# Sata_Drives.net
KiCad netlist of a schematic drawn in Altium Designer
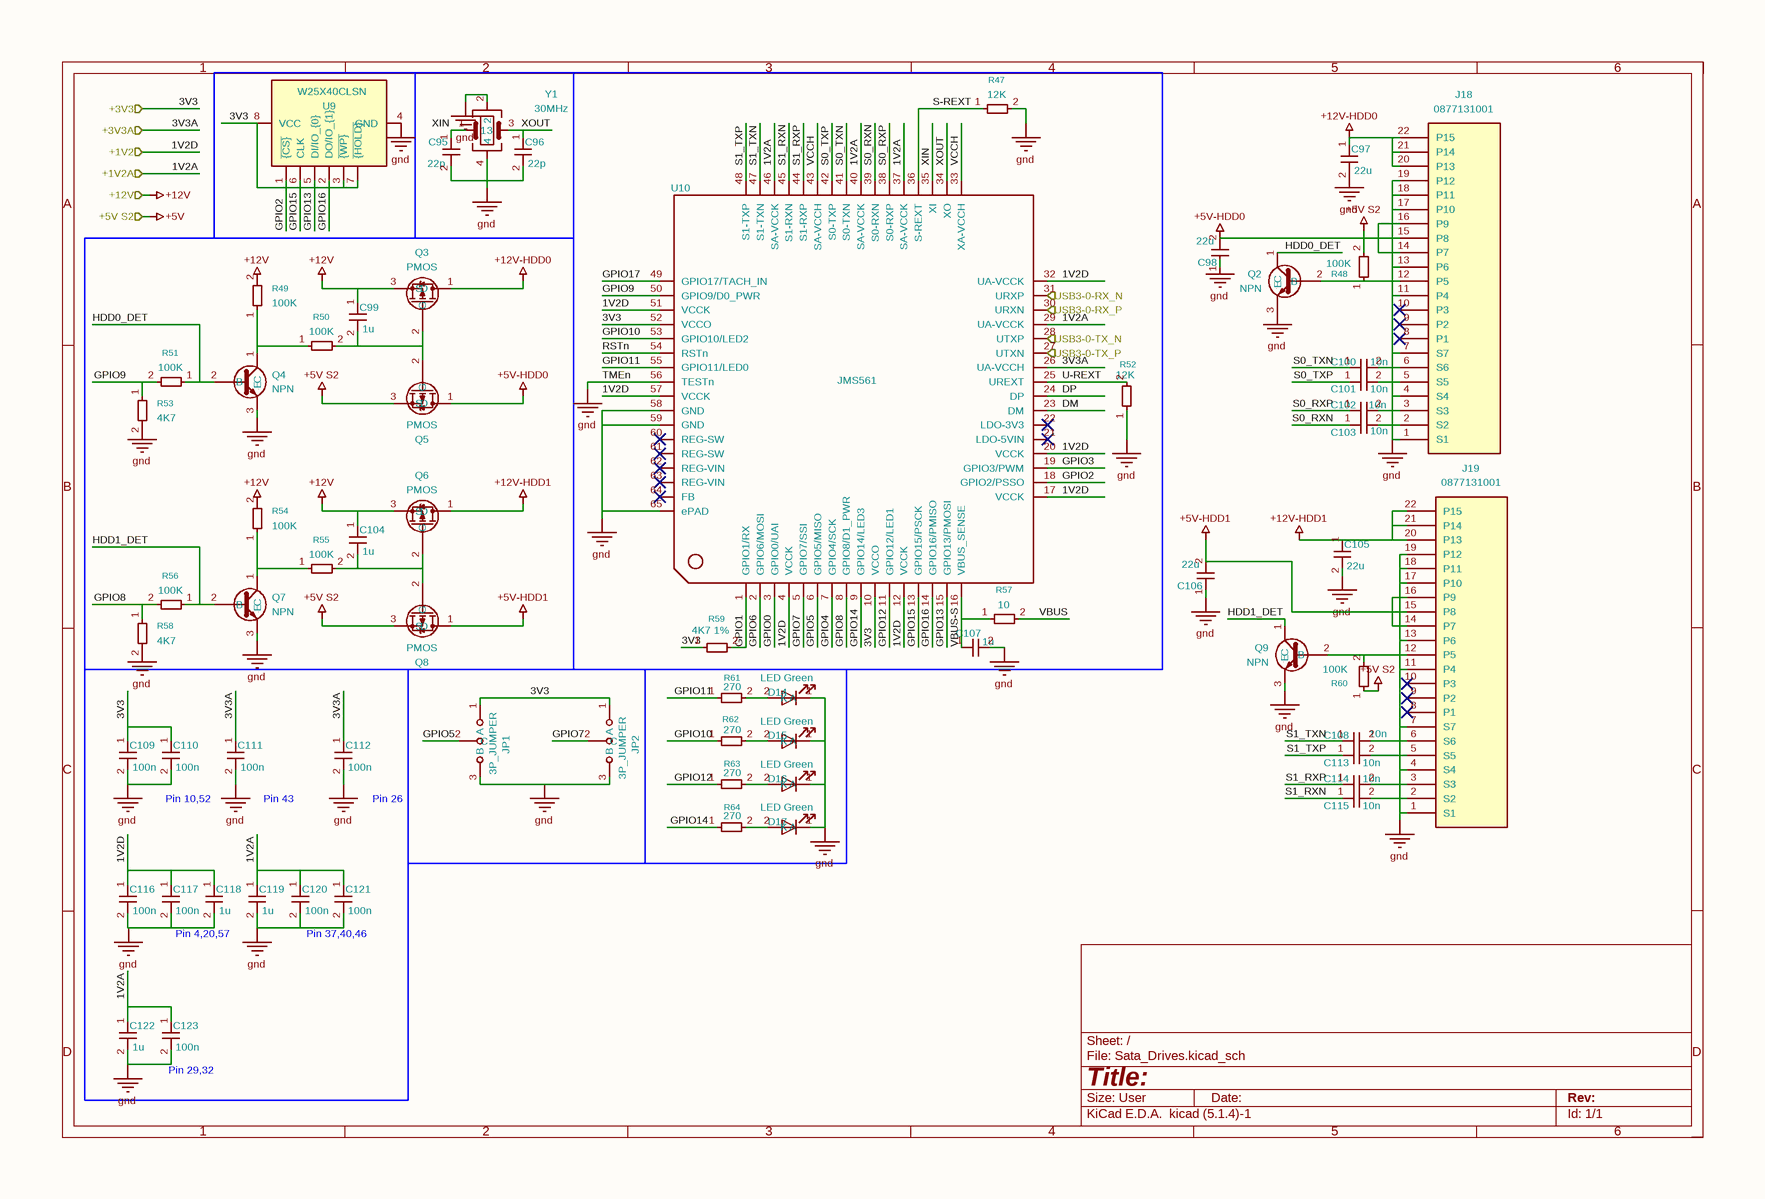
[diagram p0: Sata_Drives.SchDoc]

(export (version "E")
  (design (tool "Eeschema 10.0.6"))
  (components
    (comp (ref "C95")
      (value "22p")
      (description "Unpolarized capacitor, small symbol")
      (libsource (lib "Device") (part "C_Small"))
    )
    (comp (ref "C96")
      (value "22p")
      (description "Unpolarized capacitor, small symbol")
      (libsource (lib "Device") (part "C_Small"))
    )
    (comp (ref "C97")
      (value "22u")
      (description "Unpolarized capacitor, small symbol")
      (libsource (lib "Device") (part "C_Small"))
    )
    (comp (ref "C98")
      (value "22u")
      (description "Unpolarized capacitor, small symbol")
      (libsource (lib "Device") (part "C_Small"))
    )
    (comp (ref "C99")
      (value "1u")
      (description "Unpolarized capacitor, small symbol")
      (libsource (lib "Device") (part "C_Small"))
    )
    (comp (ref "C100")
      (value "10n")
      (description "Unpolarized capacitor, small symbol")
      (libsource (lib "Device") (part "C_Small"))
    )
    (comp (ref "C101")
      (value "10n")
      (description "Unpolarized capacitor, small symbol")
      (libsource (lib "Device") (part "C_Small"))
    )
    (comp (ref "C102")
      (value "10n")
      (description "Unpolarized capacitor, small symbol")
      (libsource (lib "Device") (part "C_Small"))
    )
    (comp (ref "C103")
      (value "10n")
      (description "Unpolarized capacitor, small symbol")
      (libsource (lib "Device") (part "C_Small"))
    )
    (comp (ref "C104")
      (value "1u")
      (description "Unpolarized capacitor, small symbol")
      (libsource (lib "Device") (part "C_Small"))
    )
    (comp (ref "C105")
      (value "22u")
      (description "Unpolarized capacitor, small symbol")
      (libsource (lib "Device") (part "C_Small"))
    )
    (comp (ref "C106")
      (value "22u")
      (description "Unpolarized capacitor, small symbol")
      (libsource (lib "Device") (part "C_Small"))
    )
    (comp (ref "C107")
      (value "1u")
      (description "Unpolarized capacitor, small symbol")
      (libsource (lib "Device") (part "C_Small"))
    )
    (comp (ref "C108")
      (value "10n")
      (description "Unpolarized capacitor, small symbol")
      (libsource (lib "Device") (part "C_Small"))
    )
    (comp (ref "C109")
      (value "100n")
      (description "Unpolarized capacitor, small symbol")
      (libsource (lib "Device") (part "C_Small"))
    )
    (comp (ref "C110")
      (value "100n")
      (description "Unpolarized capacitor, small symbol")
      (libsource (lib "Device") (part "C_Small"))
    )
    (comp (ref "C111")
      (value "100n")
      (description "Unpolarized capacitor, small symbol")
      (libsource (lib "Device") (part "C_Small"))
    )
    (comp (ref "C112")
      (value "100n")
      (description "Unpolarized capacitor, small symbol")
      (libsource (lib "Device") (part "C_Small"))
    )
    (comp (ref "C113")
      (value "10n")
      (description "Unpolarized capacitor, small symbol")
      (libsource (lib "Device") (part "C_Small"))
    )
    (comp (ref "C114")
      (value "10n")
      (description "Unpolarized capacitor, small symbol")
      (libsource (lib "Device") (part "C_Small"))
    )
    (comp (ref "C115")
      (value "10n")
      (description "Unpolarized capacitor, small symbol")
      (libsource (lib "Device") (part "C_Small"))
    )
    (comp (ref "C116")
      (value "100n")
      (description "Unpolarized capacitor, small symbol")
      (libsource (lib "Device") (part "C_Small"))
    )
    (comp (ref "C117")
      (value "100n")
      (description "Unpolarized capacitor, small symbol")
      (libsource (lib "Device") (part "C_Small"))
    )
    (comp (ref "C118")
      (value "1u")
      (description "Unpolarized capacitor, small symbol")
      (libsource (lib "Device") (part "C_Small"))
    )
    (comp (ref "C119")
      (value "1u")
      (description "Unpolarized capacitor, small symbol")
      (libsource (lib "Device") (part "C_Small"))
    )
    (comp (ref "C120")
      (value "100n")
      (description "Unpolarized capacitor, small symbol")
      (libsource (lib "Device") (part "C_Small"))
    )
    (comp (ref "C121")
      (value "100n")
      (description "Unpolarized capacitor, small symbol")
      (libsource (lib "Device") (part "C_Small"))
    )
    (comp (ref "C122")
      (value "1u")
      (description "Unpolarized capacitor, small symbol")
      (libsource (lib "Device") (part "C_Small"))
    )
    (comp (ref "C123")
      (value "100n")
      (description "Unpolarized capacitor, small symbol")
      (libsource (lib "Device") (part "C_Small"))
    )
    (comp (ref "D14") (value "LED Green") (libsource (lib "Device") (part "LED")))
    (comp (ref "D15") (value "LED Green") (libsource (lib "Device") (part "LED")))
    (comp (ref "D16") (value "LED Green") (libsource (lib "Device") (part "LED")))
    (comp (ref "D17") (value "LED Green") (libsource (lib "Device") (part "LED")))
    (comp (ref "J18")
      (value "0877131001")
      (description "CONN RCPT 22POS STR .05\" SMD AU")
      (libsource (lib "0877131001") (part "0877131001"))
    )
    (comp (ref "J19")
      (value "0877131001")
      (description "CONN RCPT 22POS STR .05\" SMD AU")
      (libsource (lib "0877131001") (part "0877131001"))
    )
    (comp (ref "JP1")
      (value "3P_JUMPER")
      (description "Jumper, 3-pole, pins 1+2 closed/bridged")
      (libsource (lib "Jumper") (part "Jumper_3_Bridged12"))
    )
    (comp (ref "JP2")
      (value "3P_JUMPER")
      (description "Jumper, 3-pole, pins 1+2 closed/bridged")
      (libsource (lib "Jumper") (part "Jumper_3_Bridged12"))
    )
    (comp (ref "Q2")
      (value "NPN")
      (description "Bipolar transistor symbol for simulation only, substrate tied to the emitter")
      (libsource (lib "Simulation_SPICE") (part "NPN"))
    )
    (comp (ref "Q3")
      (value "PMOS")
      (description "P-MOSFET transistor, drain/source/gate")
      (libsource (lib "Simulation_SPICE") (part "PMOS"))
    )
    (comp (ref "Q4")
      (value "NPN")
      (description "Bipolar transistor symbol for simulation only, substrate tied to the emitter")
      (libsource (lib "Simulation_SPICE") (part "NPN"))
    )
    (comp (ref "Q5")
      (value "PMOS")
      (description "P-MOSFET transistor, drain/source/gate")
      (libsource (lib "Simulation_SPICE") (part "PMOS"))
    )
    (comp (ref "Q6")
      (value "PMOS")
      (description "P-MOSFET transistor, drain/source/gate")
      (libsource (lib "Simulation_SPICE") (part "PMOS"))
    )
    (comp (ref "Q7")
      (value "NPN")
      (description "Bipolar transistor symbol for simulation only, substrate tied to the emitter")
      (libsource (lib "Simulation_SPICE") (part "NPN"))
    )
    (comp (ref "Q8")
      (value "PMOS")
      (description "P-MOSFET transistor, drain/source/gate")
      (libsource (lib "Simulation_SPICE") (part "PMOS"))
    )
    (comp (ref "Q9")
      (value "NPN")
      (description "Bipolar transistor symbol for simulation only, substrate tied to the emitter")
      (libsource (lib "Simulation_SPICE") (part "NPN"))
    )
    (comp (ref "R47")
      (value "12K")
      (description "Resistor, small symbol")
      (libsource (lib "") (part "R_Small_1"))
    )
    (comp (ref "R48")
      (value "100K")
      (description "Resistor, small symbol")
      (libsource (lib "Device") (part "R_Small"))
    )
    (comp (ref "R49")
      (value "100K")
      (description "Resistor, small symbol")
      (libsource (lib "Device") (part "R_Small"))
    )
    (comp (ref "R50")
      (value "100K")
      (description "Resistor, small symbol")
      (libsource (lib "") (part "R_Small_1"))
    )
    (comp (ref "R51")
      (value "100K")
      (description "Resistor, small symbol")
      (libsource (lib "") (part "R_Small_2"))
    )
    (comp (ref "R52")
      (value "12K")
      (description "Resistor, small symbol")
      (libsource (lib "Device") (part "R_Small"))
    )
    (comp (ref "R53")
      (value "4K7")
      (description "Resistor, small symbol")
      (libsource (lib "") (part "R_Small_3"))
    )
    (comp (ref "R54")
      (value "100K")
      (description "Resistor, small symbol")
      (libsource (lib "Device") (part "R_Small"))
    )
    (comp (ref "R55")
      (value "100K")
      (description "Resistor, small symbol")
      (libsource (lib "") (part "R_Small_1"))
    )
    (comp (ref "R56")
      (value "100K")
      (description "Resistor, small symbol")
      (libsource (lib "") (part "R_Small_2"))
    )
    (comp (ref "R57")
      (value "10")
      (description "Resistor, small symbol")
      (libsource (lib "") (part "R_Small_1"))
    )
    (comp (ref "R58")
      (value "4K7")
      (description "Resistor, small symbol")
      (libsource (lib "") (part "R_Small_3"))
    )
    (comp (ref "R59")
      (value "4K7 1%")
      (description "Resistor, small symbol")
      (libsource (lib "") (part "R_Small_1"))
    )
    (comp (ref "R60")
      (value "100K")
      (description "Resistor, small symbol")
      (libsource (lib "Device") (part "R_Small"))
    )
    (comp (ref "R61")
      (value "270")
      (description "Resistor, small symbol")
      (libsource (lib "") (part "R_Small_1"))
    )
    (comp (ref "R62")
      (value "270")
      (description "Resistor, small symbol")
      (libsource (lib "") (part "R_Small_1"))
    )
    (comp (ref "R63")
      (value "270")
      (description "Resistor, small symbol")
      (libsource (lib "") (part "R_Small_1"))
    )
    (comp (ref "R64")
      (value "270")
      (description "Resistor, small symbol")
      (libsource (lib "") (part "R_Small_1"))
    )
    (comp (ref "U9")
      (value "W25X40CLSN")
      (description "4Mbit / 512KiB Serial Flash memory, Standard/Dual I/O SPI, 2.3-3.6V, SOIC-8 (150 mil)")
      (libsource (lib "Memory_Flash") (part "W25X40CLSN"))
    )
    (comp (ref "U10") (value "JMS561") (libsource (lib "JMS561") (part "JMS561")))
    (comp (ref "Y1")
      (value "30MHz")
      (description "Four pin crystal, GND on pins 2 and 4")
      (libsource (lib "Device") (part "Crystal_GND24"))
    )
  )
  (nets
    (net (code "1") (name "+5V") (class "Default")
      (node (ref "Q5") (pin "3") (pinfunction "S_3") (pintype "passive"))
      (node (ref "Q8") (pin "3") (pinfunction "S_3") (pintype "passive"))
      (node (ref "R48") (pin "2") (pinfunction "2_2") (pintype "passive"))
      (node (ref "R60") (pin "1") (pinfunction "1_1") (pintype "passive"))
    )
    (net (code "2") (name "+5V-HDD0") (class "Default")
      (node (ref "C98") (pin "2") (pinfunction "2_2") (pintype "passive"))
      (node (ref "J18") (pin "14") (pinfunction "P7_14") (pintype "passive"))
      (node (ref "J18") (pin "15") (pinfunction "P8_15") (pintype "passive"))
      (node (ref "J18") (pin "16") (pinfunction "P9_16") (pintype "passive"))
      (node (ref "Q5") (pin "1") (pinfunction "D_1") (pintype "passive"))
    )
    (net (code "3") (name "+5V-HDD1") (class "Default")
      (node (ref "C106") (pin "2") (pinfunction "2_2") (pintype "passive"))
      (node (ref "J19") (pin "14") (pinfunction "P7_14") (pintype "passive"))
      (node (ref "J19") (pin "15") (pinfunction "P8_15") (pintype "passive"))
      (node (ref "J19") (pin "16") (pinfunction "P9_16") (pintype "passive"))
      (node (ref "Q8") (pin "1") (pinfunction "D_1") (pintype "passive"))
    )
    (net (code "4") (name "+12V") (class "Default")
      (node (ref "C104") (pin "1") (pinfunction "1_1") (pintype "passive"))
      (node (ref "C99") (pin "1") (pinfunction "1_1") (pintype "passive"))
      (node (ref "Q3") (pin "3") (pinfunction "S_3") (pintype "passive"))
      (node (ref "Q6") (pin "3") (pinfunction "S_3") (pintype "passive"))
      (node (ref "R49") (pin "2") (pinfunction "2_2") (pintype "passive"))
      (node (ref "R54") (pin "2") (pinfunction "2_2") (pintype "passive"))
    )
    (net (code "5") (name "+12V-HDD0") (class "Default")
      (node (ref "C97") (pin "1") (pinfunction "1_1") (pintype "passive"))
      (node (ref "J18") (pin "20") (pinfunction "P13_20") (pintype "passive"))
      (node (ref "J18") (pin "21") (pinfunction "P14_21") (pintype "passive"))
      (node (ref "J18") (pin "22") (pinfunction "P15_22") (pintype "passive"))
      (node (ref "Q3") (pin "1") (pinfunction "D_1") (pintype "passive"))
    )
    (net (code "6") (name "+12V-HDD1") (class "Default")
      (node (ref "C105") (pin "1") (pinfunction "1_1") (pintype "passive"))
      (node (ref "J19") (pin "20") (pinfunction "P13_20") (pintype "passive"))
      (node (ref "J19") (pin "21") (pinfunction "P14_21") (pintype "passive"))
      (node (ref "J19") (pin "22") (pinfunction "P15_22") (pintype "passive"))
      (node (ref "Q6") (pin "1") (pinfunction "D_1") (pintype "passive"))
    )
    (net (code "7") (name "/1V2A") (class "Default")
      (node (ref "C119") (pin "1") (pinfunction "1_1") (pintype "passive"))
      (node (ref "C120") (pin "1") (pinfunction "1_1") (pintype "passive"))
      (node (ref "C121") (pin "1") (pinfunction "1_1") (pintype "passive"))
      (node (ref "C122") (pin "1") (pinfunction "1_1") (pintype "passive"))
      (node (ref "C123") (pin "1") (pinfunction "1_1") (pintype "passive"))
      (node (ref "U10") (pin "29") (pinfunction "UA-VCCK_29") (pintype "passive"))
      (node (ref "U10") (pin "37") (pinfunction "SA-VCCK_37") (pintype "passive"))
      (node (ref "U10") (pin "40") (pinfunction "SA-VCCK_40") (pintype "passive"))
      (node (ref "U10") (pin "46") (pinfunction "SA-VCCK_46") (pintype "passive"))
    )
    (net (code "8") (name "/1V2D") (class "Default")
      (node (ref "C116") (pin "1") (pinfunction "1_1") (pintype "passive"))
      (node (ref "C117") (pin "1") (pinfunction "1_1") (pintype "passive"))
      (node (ref "C118") (pin "1") (pinfunction "1_1") (pintype "passive"))
      (node (ref "U10") (pin "12") (pinfunction "VCCK_12") (pintype "passive"))
      (node (ref "U10") (pin "17") (pinfunction "VCCK_17") (pintype "passive"))
      (node (ref "U10") (pin "20") (pinfunction "VCCK_20") (pintype "passive"))
      (node (ref "U10") (pin "32") (pinfunction "UA-VCCK_32") (pintype "passive"))
      (node (ref "U10") (pin "4") (pinfunction "VCCK_4") (pintype "passive"))
      (node (ref "U10") (pin "51") (pinfunction "VCCK_51") (pintype "passive"))
      (node (ref "U10") (pin "57") (pinfunction "VCCK_57") (pintype "passive"))
    )
    (net (code "9") (name "/3V3") (class "Default")
      (node (ref "C109") (pin "1") (pinfunction "1_1") (pintype "passive"))
      (node (ref "C110") (pin "1") (pinfunction "1_1") (pintype "passive"))
      (node (ref "JP1") (pin "1") (pinfunction "A_1") (pintype "passive"))
      (node (ref "JP2") (pin "1") (pinfunction "A_1") (pintype "passive"))
      (node (ref "R59") (pin "1") (pinfunction "1_1") (pintype "passive"))
      (node (ref "U10") (pin "10") (pinfunction "VCCO_10") (pintype "passive"))
      (node (ref "U10") (pin "52") (pinfunction "VCCO_52") (pintype "passive"))
      (node (ref "U9") (pin "3") (pinfunction "~{{WP}}_3") (pintype "passive"))
      (node (ref "U9") (pin "7") (pinfunction "~{{HOLD}}_7") (pintype "passive"))
      (node (ref "U9") (pin "8") (pinfunction "VCC_8") (pintype "passive"))
    )
    (net (code "10") (name "/3V3A") (class "Default")
      (node (ref "C111") (pin "1") (pinfunction "1_1") (pintype "passive"))
      (node (ref "C112") (pin "1") (pinfunction "1_1") (pintype "passive"))
      (node (ref "U10") (pin "26") (pinfunction "UA-VCCH_26") (pintype "passive"))
    )
    (net (code "11") (name "/DM") (class "Default")
      (node (ref "U10") (pin "23") (pinfunction "DM_23") (pintype "passive"))
    )
    (net (code "12") (name "/DP") (class "Default")
      (node (ref "U10") (pin "24") (pinfunction "DP_24") (pintype "passive"))
    )
    (net (code "13") (name "/GPIO0") (class "Default")
      (node (ref "U10") (pin "3") (pinfunction "GPIO0/UAI_3") (pintype "passive"))
    )
    (net (code "14") (name "/GPIO1") (class "Default")
      (node (ref "R59") (pin "2") (pinfunction "2_2") (pintype "passive"))
      (node (ref "U10") (pin "1") (pinfunction "GPIO1/RX_1") (pintype "passive"))
    )
    (net (code "15") (name "/GPIO2") (class "Default")
      (node (ref "U10") (pin "18") (pinfunction "GPIO2/PSSO_18") (pintype "passive"))
      (node (ref "U9") (pin "1") (pinfunction "~{{CS}}_1") (pintype "passive"))
    )
    (net (code "16") (name "/GPIO3") (class "Default")
      (node (ref "U10") (pin "19") (pinfunction "GPIO3/PWM_19") (pintype "passive"))
    )
    (net (code "17") (name "/GPIO4") (class "Default")
      (node (ref "U10") (pin "7") (pinfunction "GPIO4/SCK_7") (pintype "passive"))
    )
    (net (code "18") (name "/GPIO5") (class "Default")
      (node (ref "JP1") (pin "2") (pinfunction "C_2") (pintype "passive"))
      (node (ref "U10") (pin "6") (pinfunction "GPIO5/MISO_6") (pintype "passive"))
    )
    (net (code "19") (name "/GPIO6") (class "Default")
      (node (ref "U10") (pin "2") (pinfunction "GPIO6/MOSI_2") (pintype "passive"))
    )
    (net (code "20") (name "/GPIO7") (class "Default")
      (node (ref "JP2") (pin "2") (pinfunction "C_2") (pintype "passive"))
      (node (ref "U10") (pin "5") (pinfunction "GPIO7/SSI_5") (pintype "passive"))
    )
    (net (code "21") (name "/GPIO8") (class "Default")
      (node (ref "R56") (pin "2") (pinfunction "2_2") (pintype "passive"))
      (node (ref "R58") (pin "1") (pinfunction "1_1") (pintype "passive"))
      (node (ref "U10") (pin "8") (pinfunction "GPIO8/D1_PWR_8") (pintype "passive"))
    )
    (net (code "22") (name "/GPIO9") (class "Default")
      (node (ref "R51") (pin "2") (pinfunction "2_2") (pintype "passive"))
      (node (ref "R53") (pin "1") (pinfunction "1_1") (pintype "passive"))
      (node (ref "U10") (pin "50") (pinfunction "GPIO9/D0_PWR_50") (pintype "passive"))
    )
    (net (code "23") (name "/GPIO10") (class "Default")
      (node (ref "R62") (pin "1") (pinfunction "1_1") (pintype "passive"))
      (node (ref "U10") (pin "53") (pinfunction "GPIO10/LED2_53") (pintype "passive"))
    )
    (net (code "24") (name "/GPIO11") (class "Default")
      (node (ref "R61") (pin "1") (pinfunction "1_1") (pintype "passive"))
      (node (ref "U10") (pin "55") (pinfunction "GPIO11/LED0_55") (pintype "passive"))
    )
    (net (code "25") (name "/GPIO12") (class "Default")
      (node (ref "R63") (pin "1") (pinfunction "1_1") (pintype "passive"))
      (node (ref "U10") (pin "11") (pinfunction "GPIO12/LED1_11") (pintype "passive"))
    )
    (net (code "26") (name "/GPIO13") (class "Default")
      (node (ref "U10") (pin "15") (pinfunction "GPIO13/PMOSI_15") (pintype "passive"))
      (node (ref "U9") (pin "5") (pinfunction "DI/IO_{0}_5") (pintype "passive"))
    )
    (net (code "27") (name "/GPIO14") (class "Default")
      (node (ref "R64") (pin "1") (pinfunction "1_1") (pintype "passive"))
      (node (ref "U10") (pin "9") (pinfunction "GPIO14/LED3_9") (pintype "passive"))
    )
    (net (code "28") (name "/GPIO15") (class "Default")
      (node (ref "U10") (pin "13") (pinfunction "GPIO15/PSCK_13") (pintype "passive"))
      (node (ref "U9") (pin "6") (pinfunction "CLK_6") (pintype "passive"))
    )
    (net (code "29") (name "/GPIO16") (class "Default")
      (node (ref "U10") (pin "14") (pinfunction "GPIO16/PMISO_14") (pintype "passive"))
      (node (ref "U9") (pin "2") (pinfunction "DO/IO_{1}_2") (pintype "passive"))
    )
    (net (code "30") (name "/GPIO17") (class "Default")
      (node (ref "U10") (pin "49") (pinfunction "GPIO17/TACH_IN_49") (pintype "passive"))
    )
    (net (code "31") (name "/HDD0_DET") (class "Default")
      (node (ref "Q2") (pin "1") (pinfunction "C_1") (pintype "passive"))
      (node (ref "Q4") (pin "2") (pinfunction "B_2") (pintype "passive"))
      (node (ref "R51") (pin "1") (pinfunction "1_1") (pintype "passive"))
    )
    (net (code "32") (name "/HDD1_DET") (class "Default")
      (node (ref "Q7") (pin "2") (pinfunction "B_2") (pintype "passive"))
      (node (ref "Q9") (pin "1") (pinfunction "C_1") (pintype "passive"))
      (node (ref "R56") (pin "1") (pinfunction "1_1") (pintype "passive"))
    )
    (net (code "33") (name "/RSTn") (class "Default")
      (node (ref "U10") (pin "54") (pinfunction "RSTn_54") (pintype "passive"))
    )
    (net (code "34") (name "/S-REXT") (class "Default")
      (node (ref "R47") (pin "1") (pinfunction "1_1") (pintype "passive"))
      (node (ref "U10") (pin "36") (pinfunction "S-REXT_36") (pintype "passive"))
    )
    (net (code "35") (name "/S0_RXN") (class "Default")
      (node (ref "C103") (pin "1") (pinfunction "1_1") (pintype "passive"))
      (node (ref "U10") (pin "39") (pinfunction "S0-RXN_39") (pintype "passive"))
    )
    (net (code "36") (name "/S0_RXP") (class "Default")
      (node (ref "C102") (pin "1") (pinfunction "1_1") (pintype "passive"))
      (node (ref "U10") (pin "38") (pinfunction "S0-RXP_38") (pintype "passive"))
    )
    (net (code "37") (name "/S0_TXN") (class "Default")
      (node (ref "C100") (pin "1") (pinfunction "1_1") (pintype "passive"))
      (node (ref "U10") (pin "41") (pinfunction "S0-TXN_41") (pintype "passive"))
    )
    (net (code "38") (name "/S0_TXP") (class "Default")
      (node (ref "C101") (pin "1") (pinfunction "1_1") (pintype "passive"))
      (node (ref "U10") (pin "42") (pinfunction "S0-TXP_42") (pintype "passive"))
    )
    (net (code "39") (name "/S1_RXN") (class "Default")
      (node (ref "C115") (pin "1") (pinfunction "1_1") (pintype "passive"))
      (node (ref "U10") (pin "45") (pinfunction "S1-RXN_45") (pintype "passive"))
    )
    (net (code "40") (name "/S1_RXP") (class "Default")
      (node (ref "C114") (pin "1") (pinfunction "1_1") (pintype "passive"))
      (node (ref "U10") (pin "44") (pinfunction "S1-RXP_44") (pintype "passive"))
    )
    (net (code "41") (name "/S1_TXN") (class "Default")
      (node (ref "C108") (pin "1") (pinfunction "1_1") (pintype "passive"))
      (node (ref "U10") (pin "47") (pinfunction "S1-TXN_47") (pintype "passive"))
    )
    (net (code "42") (name "/S1_TXP") (class "Default")
      (node (ref "C113") (pin "1") (pinfunction "1_1") (pintype "passive"))
      (node (ref "U10") (pin "48") (pinfunction "S1-TXP_48") (pintype "passive"))
    )
    (net (code "43") (name "/U-REXT") (class "Default")
      (node (ref "R52") (pin "2") (pinfunction "2_2") (pintype "passive"))
      (node (ref "U10") (pin "25") (pinfunction "UREXT_25") (pintype "passive"))
    )
    (net (code "44") (name "/USB3-0-RX_N") (class "Default")
      (node (ref "U10") (pin "31") (pinfunction "URXP_31") (pintype "passive"))
    )
    (net (code "45") (name "/USB3-0-RX_P") (class "Default")
      (node (ref "U10") (pin "30") (pinfunction "URXN_30") (pintype "passive"))
    )
    (net (code "46") (name "/USB3-0-TX_N") (class "Default")
      (node (ref "U10") (pin "28") (pinfunction "UTXP_28") (pintype "passive"))
    )
    (net (code "47") (name "/USB3-0-TX_P") (class "Default")
      (node (ref "U10") (pin "27") (pinfunction "UTXN_27") (pintype "passive"))
    )
    (net (code "48") (name "/VBUS") (class "Default")
      (node (ref "R57") (pin "2") (pinfunction "2_2") (pintype "passive"))
    )
    (net (code "49") (name "/VBUS-S") (class "Default")
      (node (ref "C107") (pin "1") (pinfunction "1_1") (pintype "passive"))
      (node (ref "R57") (pin "1") (pinfunction "1_1") (pintype "passive"))
      (node (ref "U10") (pin "16") (pinfunction "VBUS_SENSE_16") (pintype "passive"))
    )
    (net (code "50") (name "/VCCH") (class "Default")
      (node (ref "U10") (pin "33") (pinfunction "XA-VCCH_33") (pintype "passive"))
      (node (ref "U10") (pin "43") (pinfunction "SA-VCCH_43") (pintype "passive"))
    )
    (net (code "51") (name "/XIN") (class "Default")
      (node (ref "C95") (pin "1") (pinfunction "1_1") (pintype "passive"))
      (node (ref "U10") (pin "35") (pinfunction "XI_35") (pintype "passive"))
      (node (ref "Y1") (pin "1") (pinfunction "1_1") (pintype "passive"))
    )
    (net (code "52") (name "/XOUT") (class "Default")
      (node (ref "C96") (pin "1") (pinfunction "1_1") (pintype "passive"))
      (node (ref "U10") (pin "34") (pinfunction "XO_34") (pintype "passive"))
      (node (ref "Y1") (pin "3") (pinfunction "3_3") (pintype "passive"))
    )
    (net (code "53") (name "Net-(D14-A)") (class "Default")
      (node (ref "D14") (pin "2") (pinfunction "A_2") (pintype "passive"))
      (node (ref "R61") (pin "2") (pinfunction "2_2") (pintype "passive"))
    )
    (net (code "54") (name "Net-(D15-A)") (class "Default")
      (node (ref "D15") (pin "2") (pinfunction "A_2") (pintype "passive"))
      (node (ref "R62") (pin "2") (pinfunction "2_2") (pintype "passive"))
    )
    (net (code "55") (name "Net-(D16-A)") (class "Default")
      (node (ref "D16") (pin "2") (pinfunction "A_2") (pintype "passive"))
      (node (ref "R63") (pin "2") (pinfunction "2_2") (pintype "passive"))
    )
    (net (code "56") (name "Net-(D17-A)") (class "Default")
      (node (ref "D17") (pin "2") (pinfunction "A_2") (pintype "passive"))
      (node (ref "R64") (pin "2") (pinfunction "2_2") (pintype "passive"))
    )
    (net (code "57") (name "Net-(J18-P5)") (class "Default")
      (node (ref "J18") (pin "12") (pinfunction "P5_12") (pintype "passive"))
      (node (ref "Q2") (pin "2") (pinfunction "B_2") (pintype "passive"))
      (node (ref "R48") (pin "1") (pinfunction "1_1") (pintype "passive"))
    )
    (net (code "58") (name "Net-(J18-S2)") (class "Default")
      (node (ref "C103") (pin "2") (pinfunction "2_2") (pintype "passive"))
      (node (ref "J18") (pin "2") (pinfunction "S2_2") (pintype "passive"))
    )
    (net (code "59") (name "Net-(J18-S3)") (class "Default")
      (node (ref "C102") (pin "2") (pinfunction "2_2") (pintype "passive"))
      (node (ref "J18") (pin "3") (pinfunction "S3_3") (pintype "passive"))
    )
    (net (code "60") (name "Net-(J18-S5)") (class "Default")
      (node (ref "C101") (pin "2") (pinfunction "2_2") (pintype "passive"))
      (node (ref "J18") (pin "5") (pinfunction "S5_5") (pintype "passive"))
    )
    (net (code "61") (name "Net-(J18-S6)") (class "Default")
      (node (ref "C100") (pin "2") (pinfunction "2_2") (pintype "passive"))
      (node (ref "J18") (pin "6") (pinfunction "S6_6") (pintype "passive"))
    )
    (net (code "62") (name "Net-(J19-P5)") (class "Default")
      (node (ref "J19") (pin "12") (pinfunction "P5_12") (pintype "passive"))
      (node (ref "Q9") (pin "2") (pinfunction "B_2") (pintype "passive"))
      (node (ref "R60") (pin "2") (pinfunction "2_2") (pintype "passive"))
    )
    (net (code "63") (name "Net-(J19-S2)") (class "Default")
      (node (ref "C115") (pin "2") (pinfunction "2_2") (pintype "passive"))
      (node (ref "J19") (pin "2") (pinfunction "S2_2") (pintype "passive"))
    )
    (net (code "64") (name "Net-(J19-S3)") (class "Default")
      (node (ref "C114") (pin "2") (pinfunction "2_2") (pintype "passive"))
      (node (ref "J19") (pin "3") (pinfunction "S3_3") (pintype "passive"))
    )
    (net (code "65") (name "Net-(J19-S5)") (class "Default")
      (node (ref "C113") (pin "2") (pinfunction "2_2") (pintype "passive"))
      (node (ref "J19") (pin "5") (pinfunction "S5_5") (pintype "passive"))
    )
    (net (code "66") (name "Net-(J19-S6)") (class "Default")
      (node (ref "C108") (pin "2") (pinfunction "2_2") (pintype "passive"))
      (node (ref "J19") (pin "6") (pinfunction "S6_6") (pintype "passive"))
    )
    (net (code "67") (name "Net-(Q3-G)") (class "Default")
      (node (ref "C99") (pin "2") (pinfunction "2_2") (pintype "passive"))
      (node (ref "Q3") (pin "2") (pinfunction "G_2") (pintype "passive"))
      (node (ref "Q5") (pin "2") (pinfunction "G_2") (pintype "passive"))
      (node (ref "R50") (pin "2") (pinfunction "2_2") (pintype "passive"))
    )
    (net (code "68") (name "Net-(Q4-C)") (class "Default")
      (node (ref "Q4") (pin "1") (pinfunction "C_1") (pintype "passive"))
      (node (ref "R49") (pin "1") (pinfunction "1_1") (pintype "passive"))
      (node (ref "R50") (pin "1") (pinfunction "1_1") (pintype "passive"))
    )
    (net (code "69") (name "Net-(Q6-G)") (class "Default")
      (node (ref "C104") (pin "2") (pinfunction "2_2") (pintype "passive"))
      (node (ref "Q6") (pin "2") (pinfunction "G_2") (pintype "passive"))
      (node (ref "Q8") (pin "2") (pinfunction "G_2") (pintype "passive"))
      (node (ref "R55") (pin "2") (pinfunction "2_2") (pintype "passive"))
    )
    (net (code "70") (name "Net-(Q7-C)") (class "Default")
      (node (ref "Q7") (pin "1") (pinfunction "C_1") (pintype "passive"))
      (node (ref "R54") (pin "1") (pinfunction "1_1") (pintype "passive"))
      (node (ref "R55") (pin "1") (pinfunction "1_1") (pintype "passive"))
    )
    (net (code "71") (name "gnd") (class "Default")
      (node (ref "C105") (pin "2") (pinfunction "2_2") (pintype "passive"))
      (node (ref "C106") (pin "1") (pinfunction "1_1") (pintype "passive"))
      (node (ref "C107") (pin "2") (pinfunction "2_2") (pintype "passive"))
      (node (ref "C109") (pin "2") (pinfunction "2_2") (pintype "passive"))
      (node (ref "C110") (pin "2") (pinfunction "2_2") (pintype "passive"))
      (node (ref "C111") (pin "2") (pinfunction "2_2") (pintype "passive"))
      (node (ref "C112") (pin "2") (pinfunction "2_2") (pintype "passive"))
      (node (ref "C116") (pin "2") (pinfunction "2_2") (pintype "passive"))
      (node (ref "C117") (pin "2") (pinfunction "2_2") (pintype "passive"))
      (node (ref "C118") (pin "2") (pinfunction "2_2") (pintype "passive"))
      (node (ref "C119") (pin "2") (pinfunction "2_2") (pintype "passive"))
      (node (ref "C120") (pin "2") (pinfunction "2_2") (pintype "passive"))
      (node (ref "C121") (pin "2") (pinfunction "2_2") (pintype "passive"))
      (node (ref "C122") (pin "2") (pinfunction "2_2") (pintype "passive"))
      (node (ref "C123") (pin "2") (pinfunction "2_2") (pintype "passive"))
      (node (ref "C95") (pin "2") (pinfunction "2_2") (pintype "passive"))
      (node (ref "C96") (pin "2") (pinfunction "2_2") (pintype "passive"))
      (node (ref "C97") (pin "2") (pinfunction "2_2") (pintype "passive"))
      (node (ref "C98") (pin "1") (pinfunction "1_1") (pintype "passive"))
      (node (ref "D14") (pin "1") (pinfunction "K_1") (pintype "passive"))
      (node (ref "D15") (pin "1") (pinfunction "K_1") (pintype "passive"))
      (node (ref "D16") (pin "1") (pinfunction "K_1") (pintype "passive"))
      (node (ref "D17") (pin "1") (pinfunction "K_1") (pintype "passive"))
      (node (ref "J18") (pin "1") (pinfunction "S1_1") (pintype "passive"))
      (node (ref "J18") (pin "11") (pinfunction "P4_11") (pintype "passive"))
      (node (ref "J18") (pin "13") (pinfunction "P6_13") (pintype "passive"))
      (node (ref "J18") (pin "17") (pinfunction "P10_17") (pintype "passive"))
      (node (ref "J18") (pin "18") (pinfunction "P11_18") (pintype "passive"))
      (node (ref "J18") (pin "19") (pinfunction "P12_19") (pintype "passive"))
      (node (ref "J18") (pin "4") (pinfunction "S4_4") (pintype "passive"))
      (node (ref "J18") (pin "7") (pinfunction "S7_7") (pintype "passive"))
      (node (ref "J19") (pin "1") (pinfunction "S1_1") (pintype "passive"))
      (node (ref "J19") (pin "11") (pinfunction "P4_11") (pintype "passive"))
      (node (ref "J19") (pin "13") (pinfunction "P6_13") (pintype "passive"))
      (node (ref "J19") (pin "17") (pinfunction "P10_17") (pintype "passive"))
      (node (ref "J19") (pin "18") (pinfunction "P11_18") (pintype "passive"))
      (node (ref "J19") (pin "19") (pinfunction "P12_19") (pintype "passive"))
      (node (ref "J19") (pin "4") (pinfunction "S4_4") (pintype "passive"))
      (node (ref "J19") (pin "7") (pinfunction "S7_7") (pintype "passive"))
      (node (ref "JP1") (pin "3") (pinfunction "B_3") (pintype "passive"))
      (node (ref "JP2") (pin "3") (pinfunction "B_3") (pintype "passive"))
      (node (ref "Q2") (pin "3") (pinfunction "E_3") (pintype "passive"))
      (node (ref "Q4") (pin "3") (pinfunction "E_3") (pintype "passive"))
      (node (ref "Q7") (pin "3") (pinfunction "E_3") (pintype "passive"))
      (node (ref "Q9") (pin "3") (pinfunction "E_3") (pintype "passive"))
      (node (ref "R47") (pin "2") (pinfunction "2_2") (pintype "passive"))
      (node (ref "R52") (pin "1") (pinfunction "1_1") (pintype "passive"))
      (node (ref "R53") (pin "2") (pinfunction "2_2") (pintype "passive"))
      (node (ref "R58") (pin "2") (pinfunction "2_2") (pintype "passive"))
      (node (ref "U10") (pin "56") (pinfunction "TESTn_56") (pintype "passive"))
      (node (ref "U10") (pin "58") (pinfunction "GND_58") (pintype "passive"))
      (node (ref "U10") (pin "59") (pinfunction "GND_59") (pintype "passive"))
      (node (ref "U10") (pin "65") (pinfunction "ePAD_65") (pintype "passive"))
      (node (ref "U9") (pin "4") (pinfunction "GND_4") (pintype "passive"))
      (node (ref "Y1") (pin "2") (pinfunction "2_2") (pintype "passive"))
      (node (ref "Y1") (pin "4") (pinfunction "4_4") (pintype "passive"))
    )
    (net (code "72") (name "unconnected-(J18-P1-Pad8)") (class "Default")
      (node (ref "J18") (pin "8") (pinfunction "P1_8") (pintype "passive+no_connect"))
    )
    (net (code "73") (name "unconnected-(J18-P2-Pad9)") (class "Default")
      (node (ref "J18") (pin "9") (pinfunction "P2_9") (pintype "passive+no_connect"))
    )
    (net (code "74") (name "unconnected-(J18-P3-Pad10)") (class "Default")
      (node (ref "J18") (pin "10") (pinfunction "P3_10") (pintype "passive+no_connect"))
    )
    (net (code "75") (name "unconnected-(J19-P1-Pad8)") (class "Default")
      (node (ref "J19") (pin "8") (pinfunction "P1_8") (pintype "passive+no_connect"))
    )
    (net (code "76") (name "unconnected-(J19-P2-Pad9)") (class "Default")
      (node (ref "J19") (pin "9") (pinfunction "P2_9") (pintype "passive+no_connect"))
    )
    (net (code "77") (name "unconnected-(J19-P3-Pad10)") (class "Default")
      (node (ref "J19") (pin "10") (pinfunction "P3_10") (pintype "passive+no_connect"))
    )
    (net (code "78") (name "unconnected-(U10-FB-Pad64)") (class "Default")
      (node (ref "U10") (pin "64") (pinfunction "FB_64") (pintype "passive+no_connect"))
    )
    (net (code "79") (name "unconnected-(U10-LDO-3V3-Pad22)") (class "Default")
      (node (ref "U10") (pin "22") (pinfunction "LDO-3V3_22") (pintype "passive+no_connect"))
    )
    (net (code "80") (name "unconnected-(U10-LDO-5VIN-Pad21)") (class "Default")
      (node (ref "U10") (pin "21") (pinfunction "LDO-5VIN_21") (pintype "passive+no_connect"))
    )
    (net (code "81") (name "unconnected-(U10-REG-SW-Pad60)") (class "Default")
      (node (ref "U10") (pin "60") (pinfunction "REG-SW_60") (pintype "passive+no_connect"))
    )
    (net (code "82") (name "unconnected-(U10-REG-SW-Pad61)") (class "Default")
      (node (ref "U10") (pin "61") (pinfunction "REG-SW_61") (pintype "passive+no_connect"))
    )
    (net (code "83") (name "unconnected-(U10-REG-VIN-Pad62)") (class "Default")
      (node (ref "U10") (pin "62") (pinfunction "REG-VIN_62") (pintype "passive+no_connect"))
    )
    (net (code "84") (name "unconnected-(U10-REG-VIN-Pad63)") (class "Default")
      (node (ref "U10") (pin "63") (pinfunction "REG-VIN_63") (pintype "passive+no_connect"))
    )
  )
)
